# MK12_PIR.net
KiCad netlist of a schematic drawn in EAGLE
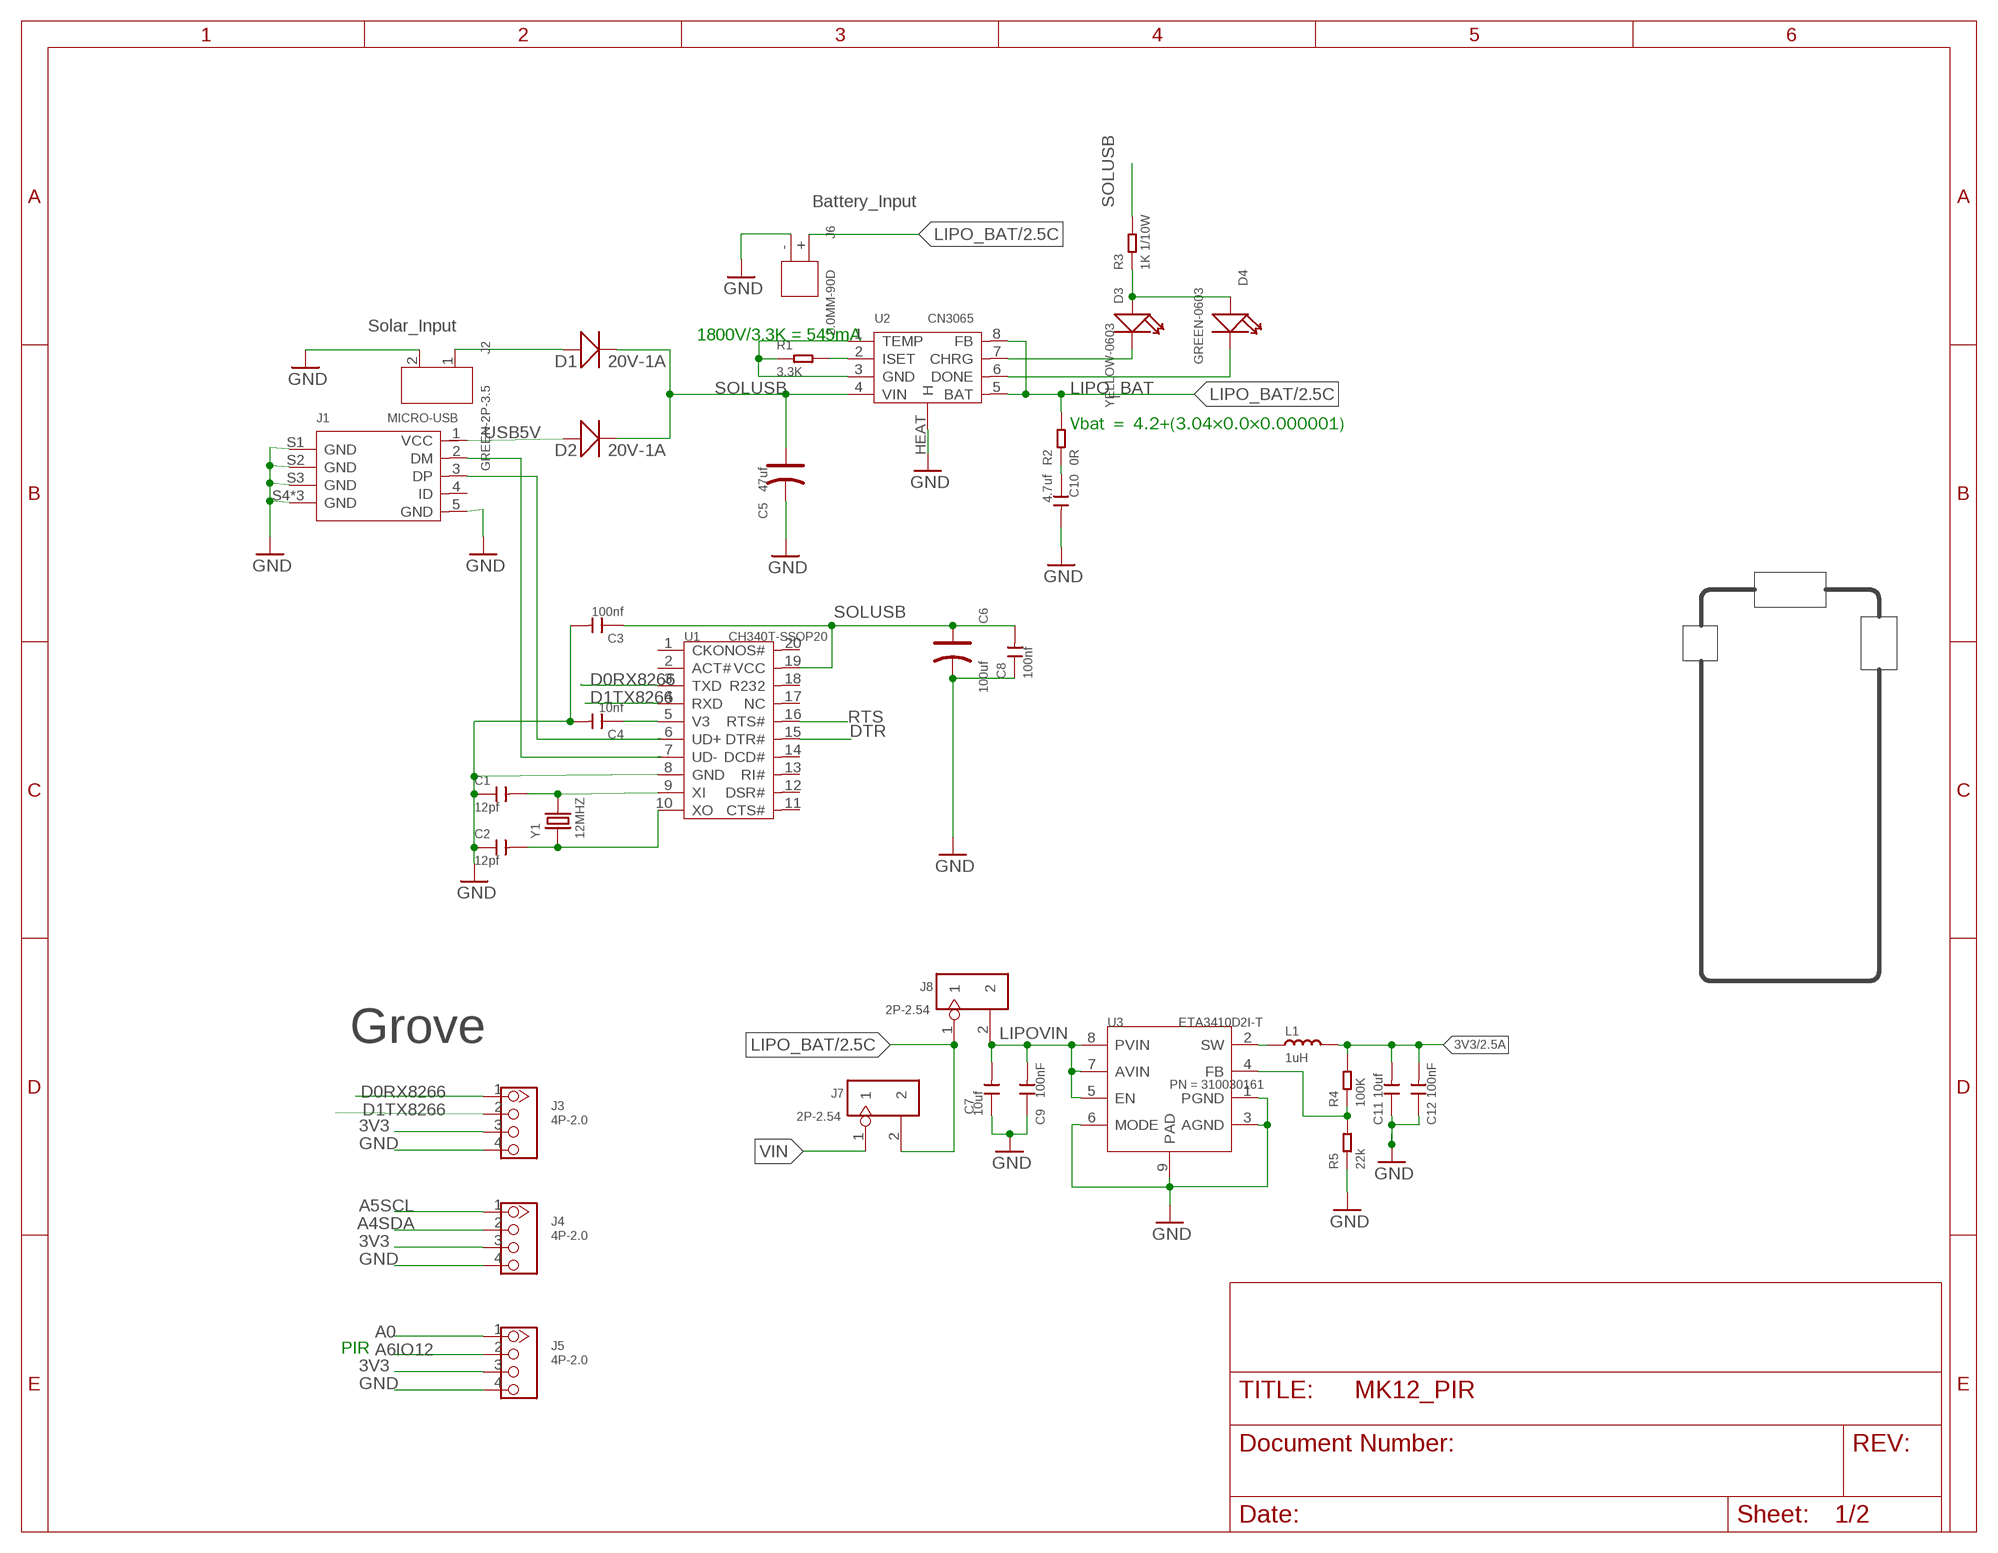
[diagram p0: schematic, sheet 1]
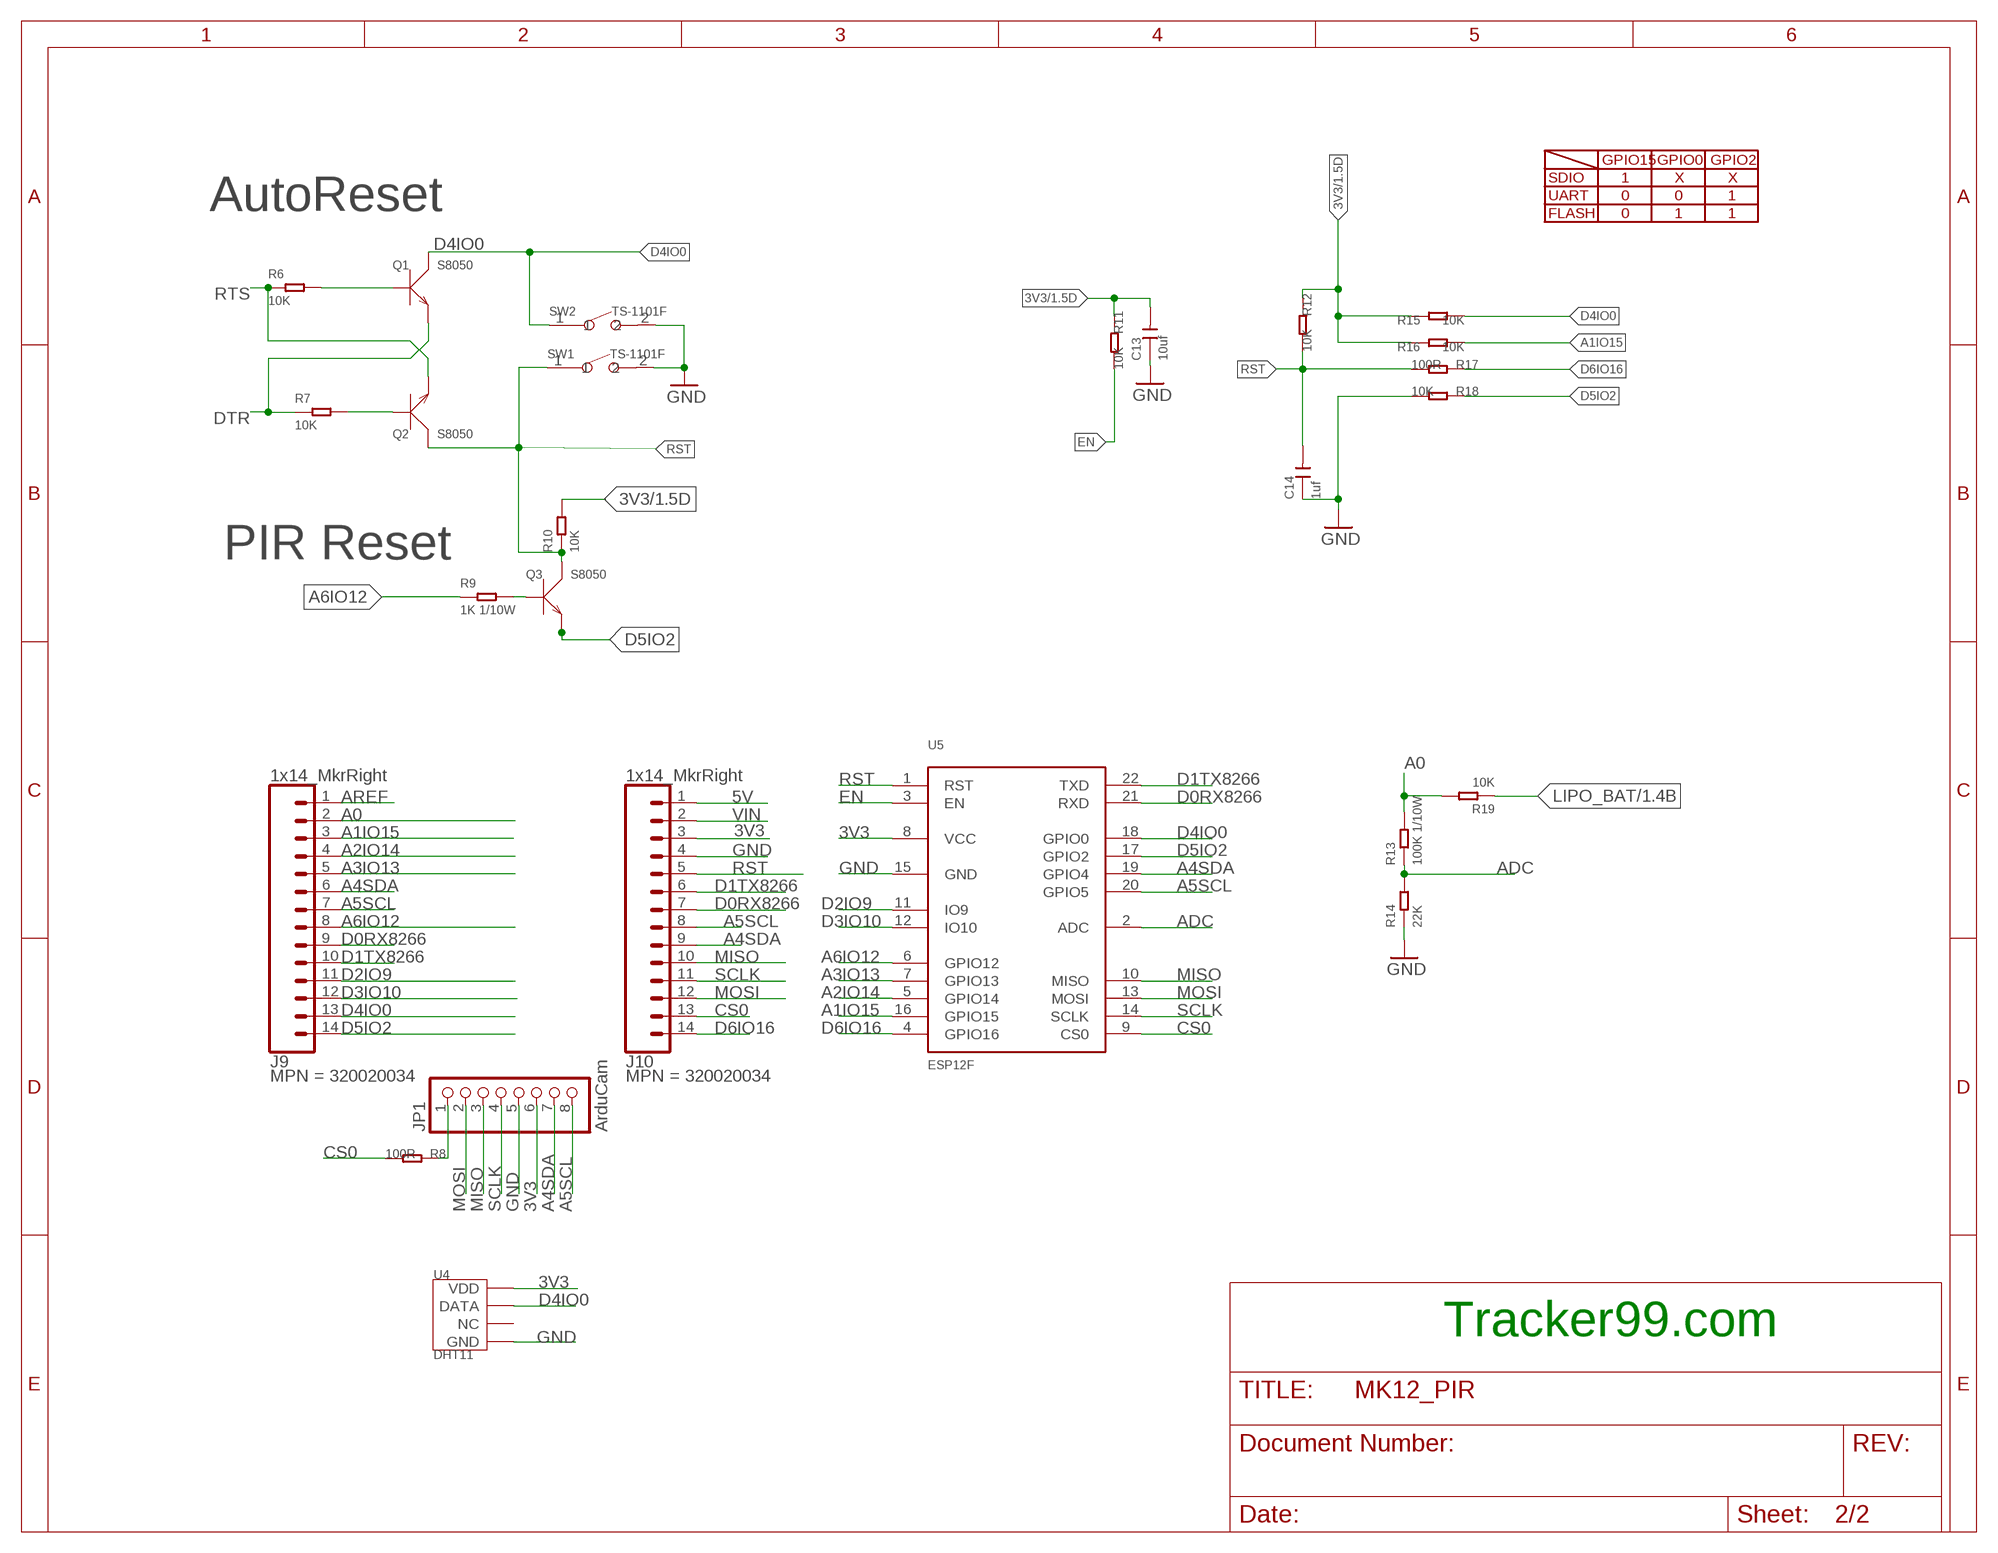
[diagram p1: schematic, sheet 2]

(export (version "E")
  (design (tool "Eeschema 10.0.6"))
  (components
    (comp (ref "C1")
      (value "12pf")
      (footprint "eagle-import:C0402")
      (fields (field (name "MPN") "CC0402JRNPO9BN120"))
      (libsource (lib "eagle-import") (part "CERAMIC-12PF-50V-5%-NPO(0402)"))
    )
    (comp (ref "C2")
      (value "12pf")
      (footprint "eagle-import:C0402")
      (fields (field (name "MPN") "CC0402JRNPO9BN120"))
      (libsource (lib "eagle-import") (part "CERAMIC-12PF-50V-5%-NPO(0402)"))
    )
    (comp (ref "C3")
      (value "100nf")
      (footprint "eagle-import:C0603")
      (fields (field (name "MPN") "CC0603KRX7R9BB104"))
      (libsource (lib "eagle-import") (part "CERAMIC-100NF-50V-10%-X7R(0603)"))
    )
    (comp (ref "C4")
      (value "10nf")
      (footprint "eagle-import:C0603")
      (fields (field (name "MPN") "CC0603KRX7R9BB103"))
      (libsource (lib "eagle-import") (part "CERAMIC-10NF-50V-10%-X7R(0603)"))
    )
    (comp (ref "C5")
      (value "47uf")
      (footprint "eagle-import:AVX-A")
      (fields (field (name "MPN") "TAJA476*006#NJ"))
      (libsource (lib "eagle-import") (part "TANTALUM-SMD-47UF-6.3V(AVX-A)"))
    )
    (comp (ref "C6")
      (value "100uf")
      (footprint "eagle-import:AVX-B")
      (fields (field (name "MPN") "TAJB107M010#NJ"))
      (libsource (lib "eagle-import") (part "TANTALUM-SMD-100UF-10V(AVX-B)"))
    )
    (comp (ref "C7")
      (value "10uf")
      (footprint "eagle-import:C0805")
      (fields (field (name "MPN") "CC0805KKX5R8BB106"))
      (libsource (lib "eagle-import") (part "CERAMIC-10UF-25V-10%-X5R(0805)"))
    )
    (comp (ref "C8")
      (value "100nf")
      (footprint "eagle-import:C0603")
      (fields (field (name "MPN") "CC0603KRX7R9BB104"))
      (libsource (lib "eagle-import") (part "CERAMIC-100NF-50V-10%-X7R(0603)"))
    )
    (comp (ref "C9")
      (value "100nF")
      (footprint "eagle-import:C0402")
      (libsource (lib "eagle-import") (part "CAP-0402"))
    )
    (comp (ref "C10")
      (value "4.7uf")
      (footprint "eagle-import:C0603")
      (fields (field (name "MPN") "CC0603KRX5R6BB475"))
      (libsource (lib "eagle-import") (part "CERAMIC-4.7UF-10V-10%-X5R(0603)"))
    )
    (comp (ref "C11")
      (value "10uf")
      (footprint "eagle-import:C0805")
      (fields (field (name "MPN") "CC0805KKX5R8BB106"))
      (libsource (lib "eagle-import") (part "CERAMIC-10UF-25V-10%-X5R(0805)"))
    )
    (comp (ref "C12")
      (value "100nF")
      (footprint "eagle-import:C0402")
      (libsource (lib "eagle-import") (part "CAP-0402"))
    )
    (comp (ref "D1")
      (value "20V-1A")
      (footprint "eagle-import:SOD-123")
      (fields (field (name "MPN") "B5819W"))
      (libsource (lib "eagle-import") (part "SMD-DIODE-SCHOTTKY-20V-1A(SOD-123)"))
    )
    (comp (ref "D2")
      (value "20V-1A")
      (footprint "eagle-import:SOD-123")
      (fields (field (name "MPN") "B5819W"))
      (libsource (lib "eagle-import") (part "SMD-DIODE-SCHOTTKY-20V-1A(SOD-123)"))
    )
    (comp (ref "D3")
      (value "YELLOW-0603")
      (footprint "eagle-import:LED-0603")
      (fields (field (name "MPN") "19-217-Y5C-AM1N1VY-3T"))
      (libsource (lib "eagle-import") (part "SMD-LED-CLEAR-YELLOW(0603)"))
    )
    (comp (ref "D4")
      (value "GREEN-0603")
      (footprint "eagle-import:LED-0603")
      (fields (field (name "MPN") "19-217-G7C-AN1P2-3T"))
      (libsource (lib "eagle-import") (part "SMD-LED-CLEAR-GREEN(0603)"))
    )
    (comp (ref "J1")
      (value "MICRO-USB")
      (footprint "eagle-import:MICRO-USB5+4P-SMD-0.65-B")
      (fields (field (name "EAGLEUP") "USB-MICROB;2.54mm"))
      (libsource (lib "eagle-import") (part "MICRO-USB5+4P'5+4P'"))
    )
    (comp (ref "J2")
      (value "GREEN-2P-3.5")
      (footprint "eagle-import:H2-3.5-7.0X7.0MM")
      (libsource (lib "eagle-import") (part "SCREW-TERMINAL-GREEN(2P-3.5)"))
    )
    (comp (ref "J3")
      (value "4P-2.0")
      (footprint "eagle-import:HW4-2.0")
      (libsource (lib "eagle-import") (part "GROVE-CONNECTOR-DIP(4P-2.0)"))
    )
    (comp (ref "J4")
      (value "4P-2.0")
      (footprint "eagle-import:HW4-2.0")
      (libsource (lib "eagle-import") (part "GROVE-CONNECTOR-DIP(4P-2.0)"))
    )
    (comp (ref "J5")
      (value "4P-2.0")
      (footprint "eagle-import:HW4-2.0")
      (libsource (lib "eagle-import") (part "GROVE-CONNECTOR-DIP(4P-2.0)"))
    )
    (comp (ref "J6")
      (value "2.0MM-90D")
      (footprint "eagle-import:H2-2.0-90D")
      (libsource (lib "eagle-import") (part "CONN-HEADER-PH-SIDE-(2P-2.0MM)'90D'"))
    )
    (comp (ref "J7")
      (value "2P-2.54")
      (footprint "eagle-import:H2-2.54")
      (fields (field (name "MPN") "P125-1102A0BS116A3"))
      (libsource (lib "eagle-import") (part "DIP-WHITE-MALE-HEADER-VERT(2P-2.54)"))
    )
    (comp (ref "J8")
      (value "2P-2.54")
      (footprint "eagle-import:H2-2.54")
      (fields (field (name "MPN") "P125-1102A0BS116A3"))
      (libsource (lib "eagle-import") (part "DIP-WHITE-MALE-HEADER-VERT(2P-2.54)"))
    )
    (comp (ref "L1")
      (value "1uH")
      (footprint "eagle-import:L0603")
      (libsource (lib "eagle-import") (part "INDUCTOR/FERRITE-BEAD'0603'"))
    )
    (comp (ref "R1")
      (value "3.3K")
      (footprint "eagle-import:R0603")
      (libsource (lib "eagle-import") (part "SMD-RES-3.3K-5%-1/10W(0603)"))
    )
    (comp (ref "R2")
      (value "0R")
      (footprint "eagle-import:R0603")
      (fields (field (name "MPN") "RC0603JR-070RL"))
      (libsource (lib "eagle-import") (part "SMD-RES-0R-5%-1/10W(0603)"))
    )
    (comp (ref "R3")
      (value "1K 1/10W")
      (footprint "eagle-import:R0603")
      (fields (field (name "MPN") "RC0603JR-071KL"))
      (libsource (lib "eagle-import") (part "SMD-RES-1K-5%-1/10W(0603)"))
    )
    (comp (ref "R4")
      (value "100K")
      (footprint "eagle-import:R0402")
      (fields (field (name "MPN") "RC0402FR-07100KL"))
      (libsource (lib "eagle-import") (part "SMD-RES-100K-1%-1/16W(0402)"))
    )
    (comp (ref "R5")
      (value "22k")
      (footprint "eagle-import:R0402")
      (fields (field (name "MPN") "RC0402FR-0722KL"))
      (libsource (lib "eagle-import") (part "SMD-RES-22K-1%-1/16W(0402)"))
    )
    (comp (ref "U1")
      (value "CH340T-SSOP20")
      (footprint "eagle-import:SSOP20-0.65-7.6X5.2MM")
      (fields (field (name "MPN") "CH340T"))
      (libsource (lib "eagle-import") (part "INTERFACE-CH340T(SSOP20)"))
    )
    (comp (ref "U2")
      (value "CN3065")
      (footprint "eagle-import:DFN-8")
      (libsource (lib "eagle-import") (part "PMIC-CN3065-DFN8"))
    )
    (comp (ref "U3")
      (value "ETA3410D2I-T")
      (footprint "eagle-import:DFN8G-0.5-2X2MM")
      (fields (field (name "PN") "310030161"))
      (libsource (lib "eagle-import") (part "CONVERTER-ETA3410"))
    )
    (comp (ref "Y1")
      (value "12MHZ")
      (footprint "eagle-import:X2-SMD-5.0X3.2X1.3MM")
      (fields (field (name "MPN") "5032/2P"))
      (libsource (lib "eagle-import") (part "SMD-CRYSTAL-12MHZ-20PF-20PPM-40R(2P-5.0X3.2MM)"))
    )
    (comp (ref "C13")
      (value "10uf")
      (footprint "eagle-import:C0603")
      (fields (field (name "MPN") "CC0603KRX5R6BB106"))
      (libsource (lib "eagle-import") (part "CERAMIC-10UF-10V-10%-X5R(0603)"))
    )
    (comp (ref "C14")
      (value "1uf")
      (footprint "eagle-import:C0603")
      (fields (field (name "MPN") "CC0603KRX7R8BB105"))
      (libsource (lib "eagle-import") (part "CERAMIC-1UF-25V-10%-X7R(0603)"))
    )
    (comp (ref "J9")
      (value "1x14_MkrRight")
      (footprint "eagle-import:1X14_LOCK")
      (fields (field (name "MPN") "320020034"))
      (libsource (lib "eagle-import") (part "CONN_14LOCK"))
    )
    (comp (ref "J10")
      (value "1x14_MkrRight")
      (footprint "eagle-import:1X14_LOCK")
      (fields (field (name "MPN") "320020034"))
      (libsource (lib "eagle-import") (part "CONN_14LOCK"))
    )
    (comp (ref "JP1")
      (value "ArduCam")
      (footprint "eagle-import:MILLER_1X08-LOCK")
      (libsource (lib "eagle-import") (part "MILLER_PINHD-1X8LOCK"))
    )
    (comp (ref "Q1")
      (value "S8050")
      (footprint "eagle-import:SOT-23")
      (libsource (lib "eagle-import") (part "SMD-TRANSISTORS-NPN-25V-500MW-S8050(SOT-23)"))
    )
    (comp (ref "Q2")
      (value "S8050")
      (footprint "eagle-import:SOT-23")
      (libsource (lib "eagle-import") (part "SMD-TRANSISTORS-NPN-25V-500MW-S8050(SOT-23)"))
    )
    (comp (ref "Q3")
      (value "S8050")
      (footprint "eagle-import:SOT-23")
      (libsource (lib "eagle-import") (part "SMD-TRANSISTORS-NPN-25V-500MW-S8050(SOT-23)"))
    )
    (comp (ref "R6")
      (value "10K")
      (footprint "eagle-import:R0402")
      (fields (field (name "MPN") "RC0402JR-0710KL"))
      (libsource (lib "eagle-import") (part "SMD-RES-10K-5%-1/(0402)"))
    )
    (comp (ref "R7")
      (value "10K")
      (footprint "eagle-import:R0402")
      (fields (field (name "MPN") "RC0402JR-0710KL"))
      (libsource (lib "eagle-import") (part "SMD-RES-10K-5%-1/(0402)"))
    )
    (comp (ref "R8")
      (value "100R")
      (footprint "eagle-import:R0603")
      (fields (field (name "MPN") "RC0603JR-07100RL"))
      (libsource (lib "eagle-import") (part "SMD-RES-100R-5%-1/10W(0603)"))
    )
    (comp (ref "R9")
      (value "1K 1/10W")
      (footprint "eagle-import:R0603")
      (fields (field (name "MPN") "RC0603JR-071KL"))
      (libsource (lib "eagle-import") (part "SMD-RES-1K-5%-1/10W(0603)"))
    )
    (comp (ref "R10")
      (value "10K")
      (footprint "eagle-import:R0402")
      (fields (field (name "MPN") "RC0402JR-0710KL"))
      (libsource (lib "eagle-import") (part "SMD-RES-10K-5%-1/(0402)"))
    )
    (comp (ref "R11")
      (value "10K")
      (footprint "eagle-import:SEEED-RESISTOR_R0402")
      (fields (field (name "MPN") "RC0402JR-0710KL"))
      (libsource (lib "eagle-import") (part "SEEED-RESISTOR_SMD-RES-10K-5%-1/(0402)"))
    )
    (comp (ref "R12")
      (value "10K")
      (footprint "eagle-import:SEEED-RESISTOR_R0402")
      (fields (field (name "MPN") "RC0402JR-0710KL"))
      (libsource (lib "eagle-import") (part "SEEED-RESISTOR_SMD-RES-10K-5%-1/(0402)"))
    )
    (comp (ref "R13")
      (value "100K 1/10W")
      (footprint "eagle-import:R0603")
      (fields (field (name "MPN") "RC0603JR-07100KL"))
      (libsource (lib "eagle-import") (part "SMD-RES-100K-5%-1/10W(0603)"))
    )
    (comp (ref "R14")
      (value "22K")
      (footprint "eagle-import:R0603")
      (fields (field (name "MPN") "RC0603JR-0722KL"))
      (libsource (lib "eagle-import") (part "SMD-RES-22K-5%-1/10W(0603)"))
    )
    (comp (ref "R15")
      (value "10K")
      (footprint "eagle-import:SEEED-RESISTOR_R0402")
      (fields (field (name "MPN") "RC0402JR-0710KL"))
      (libsource (lib "eagle-import") (part "SEEED-RESISTOR_SMD-RES-10K-5%-1/(0402)"))
    )
    (comp (ref "R16")
      (value "10K")
      (footprint "eagle-import:SEEED-RESISTOR_R0402")
      (fields (field (name "MPN") "RC0402JR-0710KL"))
      (libsource (lib "eagle-import") (part "SEEED-RESISTOR_SMD-RES-10K-5%-1/(0402)"))
    )
    (comp (ref "R17")
      (value "100R")
      (footprint "eagle-import:R0603")
      (fields (field (name "MPN") "RC0603JR-07100RL"))
      (libsource (lib "eagle-import") (part "SMD-RES-100R-5%-1/10W(0603)"))
    )
    (comp (ref "R18")
      (value "10K")
      (footprint "eagle-import:SEEED-RESISTOR_R0402")
      (fields (field (name "MPN") "RC0402JR-0710KL"))
      (libsource (lib "eagle-import") (part "SEEED-RESISTOR_SMD-RES-10K-5%-1/(0402)"))
    )
    (comp (ref "R19")
      (value "10K")
      (footprint "eagle-import:R0402")
      (fields (field (name "MPN") "RC0402JR-0710KL"))
      (libsource (lib "eagle-import") (part "SMD-RES-10K-5%-1/(0402)"))
    )
    (comp (ref "SW1")
      (value "TS-1101F")
      (footprint "eagle-import:SW2-5.0-6.0X3.0X4.3MM")
      (libsource (lib "eagle-import") (part "DIP-BUTTON(2P-6.0X3.0X4.3MM)-TS-1101F"))
    )
    (comp (ref "SW2")
      (value "TS-1101F")
      (footprint "eagle-import:SW2-5.0-6.0X3.0X4.3MM")
      (libsource (lib "eagle-import") (part "DIP-BUTTON(2P-6.0X3.0X4.3MM)-TS-1101F"))
    )
    (comp (ref "U4")
      (value "DHT11")
      (footprint "eagle-import:SNR4-2.54-15.5X12.0X5.5MM")
      (libsource (lib "eagle-import") (part "TEM-HUM-DHT11(4P-15.5X12.0MM)"))
    )
    (comp (ref "U5")
      (value "ESP12F")
      (footprint "eagle-import:ESP-12F")
      (libsource (lib "eagle-import") (part "ESP-12F"))
    )
  )
  (nets
    (net (code "1") (name "3V3") (class "Default")
      (node (ref "C11") (pin "2") (pinfunction "2_2") (pintype "passive"))
      (node (ref "C12") (pin "2") (pinfunction "2_2") (pintype "passive"))
      (node (ref "C13") (pin "2") (pinfunction "2_2") (pintype "passive"))
      (node (ref "J10") (pin "3") (pinfunction "3_3") (pintype "passive"))
      (node (ref "J3") (pin "3") (pinfunction "3_3") (pintype "bidirectional"))
      (node (ref "J4") (pin "3") (pinfunction "3_3") (pintype "bidirectional"))
      (node (ref "J5") (pin "3") (pinfunction "3_3") (pintype "bidirectional"))
      (node (ref "JP1") (pin "6") (pinfunction "6_6") (pintype "passive"))
      (node (ref "L1") (pin "2") (pinfunction "2_2") (pintype "passive"))
      (node (ref "R10") (pin "2") (pinfunction "2_2") (pintype "passive"))
      (node (ref "R11") (pin "1") (pinfunction "1_1") (pintype "passive"))
      (node (ref "R12") (pin "1") (pinfunction "1_1") (pintype "passive"))
      (node (ref "R15") (pin "1") (pinfunction "1_1") (pintype "passive"))
      (node (ref "R16") (pin "1") (pinfunction "1_1") (pintype "passive"))
      (node (ref "R4") (pin "2") (pinfunction "2_2") (pintype "passive"))
      (node (ref "U4") (pin "1") (pinfunction "VDD_1") (pintype "power_in"))
      (node (ref "U5") (pin "8") (pinfunction "VCC_8") (pintype "bidirectional"))
    )
    (net (code "2") (name "5V") (class "Default")
      (node (ref "J10") (pin "1") (pinfunction "1_1") (pintype "passive"))
    )
    (net (code "3") (name "A0") (class "Default")
      (node (ref "J5") (pin "1") (pinfunction "1_1") (pintype "bidirectional"))
      (node (ref "J9") (pin "2") (pinfunction "2_2") (pintype "passive"))
      (node (ref "R13") (pin "2") (pinfunction "2_2") (pintype "passive"))
      (node (ref "R19") (pin "2") (pinfunction "2_2") (pintype "passive"))
    )
    (net (code "4") (name "A1IO15") (class "Default")
      (node (ref "J9") (pin "3") (pinfunction "3_3") (pintype "passive"))
      (node (ref "R16") (pin "2") (pinfunction "2_2") (pintype "passive"))
      (node (ref "U5") (pin "16") (pinfunction "GPIO15_16") (pintype "bidirectional"))
    )
    (net (code "5") (name "A2IO14") (class "Default")
      (node (ref "J9") (pin "4") (pinfunction "4_4") (pintype "passive"))
      (node (ref "U5") (pin "5") (pinfunction "GPIO14_5") (pintype "bidirectional"))
    )
    (net (code "6") (name "A3IO13") (class "Default")
      (node (ref "J9") (pin "5") (pinfunction "5_5") (pintype "passive"))
      (node (ref "U5") (pin "7") (pinfunction "GPIO13_7") (pintype "bidirectional"))
    )
    (net (code "7") (name "A4SDA") (class "Default")
      (node (ref "J10") (pin "9") (pinfunction "9_9") (pintype "passive"))
      (node (ref "J4") (pin "2") (pinfunction "2_2") (pintype "bidirectional"))
      (node (ref "J9") (pin "6") (pinfunction "6_6") (pintype "passive"))
      (node (ref "JP1") (pin "7") (pinfunction "7_7") (pintype "passive"))
      (node (ref "U5") (pin "19") (pinfunction "GPIO4_19") (pintype "bidirectional"))
    )
    (net (code "8") (name "A5SCL") (class "Default")
      (node (ref "J10") (pin "8") (pinfunction "8_8") (pintype "passive"))
      (node (ref "J4") (pin "1") (pinfunction "1_1") (pintype "bidirectional"))
      (node (ref "J9") (pin "7") (pinfunction "7_7") (pintype "passive"))
      (node (ref "JP1") (pin "8") (pinfunction "8_8") (pintype "passive"))
      (node (ref "U5") (pin "20") (pinfunction "GPIO5_20") (pintype "bidirectional"))
    )
    (net (code "9") (name "A6IO12") (class "Default")
      (node (ref "J5") (pin "2") (pinfunction "2_2") (pintype "bidirectional"))
      (node (ref "J9") (pin "8") (pinfunction "8_8") (pintype "passive"))
      (node (ref "R9") (pin "1") (pinfunction "1_1") (pintype "passive"))
      (node (ref "U5") (pin "6") (pinfunction "GPIO12_6") (pintype "bidirectional"))
    )
    (net (code "10") (name "ADC") (class "Default")
      (node (ref "R13") (pin "1") (pinfunction "1_1") (pintype "passive"))
      (node (ref "R14") (pin "2") (pinfunction "2_2") (pintype "passive"))
      (node (ref "U5") (pin "2") (pinfunction "ADC_2") (pintype "bidirectional"))
    )
    (net (code "11") (name "AREF") (class "Default")
      (node (ref "J9") (pin "1") (pinfunction "1_1") (pintype "passive"))
    )
    (net (code "12") (name "CS0") (class "Default")
      (node (ref "J10") (pin "13") (pinfunction "13_13") (pintype "passive"))
      (node (ref "R8") (pin "2") (pinfunction "2_2") (pintype "passive"))
      (node (ref "U5") (pin "9") (pinfunction "CS0_9") (pintype "bidirectional"))
    )
    (net (code "13") (name "D0RX8266") (class "Default")
      (node (ref "J10") (pin "7") (pinfunction "7_7") (pintype "passive"))
      (node (ref "J3") (pin "1") (pinfunction "1_1") (pintype "bidirectional"))
      (node (ref "J9") (pin "9") (pinfunction "9_9") (pintype "passive"))
      (node (ref "U1") (pin "3") (pinfunction "TXD_3") (pintype "output"))
      (node (ref "U5") (pin "21") (pinfunction "RXD_21") (pintype "bidirectional"))
    )
    (net (code "14") (name "D1TX8266") (class "Default")
      (node (ref "J10") (pin "6") (pinfunction "6_6") (pintype "passive"))
      (node (ref "J3") (pin "2") (pinfunction "2_2") (pintype "bidirectional"))
      (node (ref "J9") (pin "10") (pinfunction "10_10") (pintype "passive"))
      (node (ref "U1") (pin "4") (pinfunction "RXD_4") (pintype "input"))
      (node (ref "U5") (pin "22") (pinfunction "TXD_22") (pintype "bidirectional"))
    )
    (net (code "15") (name "D2IO9") (class "Default")
      (node (ref "J9") (pin "11") (pinfunction "11_11") (pintype "passive"))
      (node (ref "U5") (pin "11") (pinfunction "IO9_11") (pintype "bidirectional"))
    )
    (net (code "16") (name "D3IO10") (class "Default")
      (node (ref "J9") (pin "12") (pinfunction "12_12") (pintype "passive"))
      (node (ref "U5") (pin "12") (pinfunction "IO10_12") (pintype "bidirectional"))
    )
    (net (code "17") (name "D4IO0") (class "Default")
      (node (ref "J9") (pin "13") (pinfunction "13_13") (pintype "passive"))
      (node (ref "Q1") (pin "3") (pinfunction "C_3") (pintype "passive"))
      (node (ref "R15") (pin "2") (pinfunction "2_2") (pintype "passive"))
      (node (ref "SW2") (pin "1") (pinfunction "1_1") (pintype "bidirectional"))
      (node (ref "U4") (pin "2") (pinfunction "DATA_2") (pintype "bidirectional"))
      (node (ref "U5") (pin "18") (pinfunction "GPIO0_18") (pintype "bidirectional"))
    )
    (net (code "18") (name "D5IO2") (class "Default")
      (node (ref "J9") (pin "14") (pinfunction "14_14") (pintype "passive"))
      (node (ref "Q3") (pin "2") (pinfunction "E_2") (pintype "passive"))
      (node (ref "R18") (pin "1") (pinfunction "1_1") (pintype "passive"))
      (node (ref "U5") (pin "17") (pinfunction "GPIO2_17") (pintype "bidirectional"))
    )
    (net (code "19") (name "D6IO16") (class "Default")
      (node (ref "J10") (pin "14") (pinfunction "14_14") (pintype "passive"))
      (node (ref "R17") (pin "1") (pinfunction "1_1") (pintype "passive"))
      (node (ref "U5") (pin "4") (pinfunction "GPIO16_4") (pintype "bidirectional"))
    )
    (net (code "20") (name "DTR") (class "Default")
      (node (ref "Q1") (pin "2") (pinfunction "E_2") (pintype "passive"))
      (node (ref "R7") (pin "1") (pinfunction "1_1") (pintype "passive"))
      (node (ref "U1") (pin "15") (pinfunction "DTR#_15") (pintype "output"))
    )
    (net (code "21") (name "EN") (class "Default")
      (node (ref "R11") (pin "2") (pinfunction "2_2") (pintype "passive"))
      (node (ref "U5") (pin "3") (pinfunction "EN_3") (pintype "bidirectional"))
    )
    (net (code "22") (name "GND") (class "Default")
      (node (ref "C1") (pin "1") (pinfunction "1_1") (pintype "passive"))
      (node (ref "C10") (pin "2") (pinfunction "2_2") (pintype "passive"))
      (node (ref "C11") (pin "1") (pinfunction "1_1") (pintype "passive"))
      (node (ref "C12") (pin "1") (pinfunction "1_1") (pintype "passive"))
      (node (ref "C13") (pin "1") (pinfunction "1_1") (pintype "passive"))
      (node (ref "C14") (pin "1") (pinfunction "1_1") (pintype "passive"))
      (node (ref "C2") (pin "1") (pinfunction "1_1") (pintype "passive"))
      (node (ref "C3") (pin "2") (pinfunction "2_2") (pintype "passive"))
      (node (ref "C4") (pin "2") (pinfunction "2_2") (pintype "passive"))
      (node (ref "C5") (pin "-") (pinfunction "-_-") (pintype "passive"))
      (node (ref "C6") (pin "-") (pinfunction "-_-") (pintype "passive"))
      (node (ref "C7") (pin "1") (pinfunction "1_1") (pintype "passive"))
      (node (ref "C8") (pin "1") (pinfunction "1_1") (pintype "passive"))
      (node (ref "C9") (pin "1") (pinfunction "1_1") (pintype "passive"))
      (node (ref "J1") (pin "5") (pinfunction "GND_5") (pintype "bidirectional"))
      (node (ref "J1") (pin "S1") (pinfunction "GND_S1") (pintype "bidirectional"))
      (node (ref "J1") (pin "S2") (pinfunction "GND_S2") (pintype "bidirectional"))
      (node (ref "J1") (pin "S3") (pinfunction "GND_S3") (pintype "bidirectional"))
      (node (ref "J1") (pin "S4") (pinfunction "GND_S4") (pintype "bidirectional"))
      (node (ref "J1") (pin "S5") (pinfunction "GND_S5") (pintype "bidirectional"))
      (node (ref "J1") (pin "S6") (pinfunction "GND_S6") (pintype "bidirectional"))
      (node (ref "J10") (pin "4") (pinfunction "4_4") (pintype "passive"))
      (node (ref "J2") (pin "2") (pinfunction "2_2") (pintype "bidirectional"))
      (node (ref "J3") (pin "4") (pinfunction "4_4") (pintype "bidirectional"))
      (node (ref "J4") (pin "4") (pinfunction "4_4") (pintype "bidirectional"))
      (node (ref "J5") (pin "4") (pinfunction "4_4") (pintype "bidirectional"))
      (node (ref "J6") (pin "-") (pinfunction "P$2_-") (pintype "bidirectional"))
      (node (ref "JP1") (pin "5") (pinfunction "5_5") (pintype "passive"))
      (node (ref "R1") (pin "1") (pinfunction "1_1") (pintype "passive"))
      (node (ref "R14") (pin "1") (pinfunction "1_1") (pintype "passive"))
      (node (ref "R18") (pin "2") (pinfunction "2_2") (pintype "passive"))
      (node (ref "R5") (pin "1") (pinfunction "1_1") (pintype "passive"))
      (node (ref "SW1") (pin "2") (pinfunction "2_2") (pintype "bidirectional"))
      (node (ref "SW2") (pin "2") (pinfunction "2_2") (pintype "bidirectional"))
      (node (ref "U1") (pin "8") (pinfunction "GND_8") (pintype "power_in"))
      (node (ref "U2") (pin "1") (pinfunction "TEMP_1") (pintype "input"))
      (node (ref "U2") (pin "3") (pinfunction "GND_3") (pintype "power_in"))
      (node (ref "U2") (pin "HEAT") (pinfunction "H_HEAT") (pintype "bidirectional"))
      (node (ref "U3") (pin "1") (pinfunction "PGND_1") (pintype "bidirectional"))
      (node (ref "U3") (pin "3") (pinfunction "AGND_3") (pintype "bidirectional"))
      (node (ref "U3") (pin "6") (pinfunction "MODE_6") (pintype "bidirectional"))
      (node (ref "U3") (pin "9") (pinfunction "PAD_9") (pintype "bidirectional"))
      (node (ref "U4") (pin "4") (pinfunction "GND_4") (pintype "power_in"))
      (node (ref "U5") (pin "15") (pinfunction "GND_15") (pintype "bidirectional"))
    )
    (net (code "23") (name "LIPOVIN") (class "Default")
      (node (ref "C7") (pin "2") (pinfunction "2_2") (pintype "passive"))
      (node (ref "C9") (pin "2") (pinfunction "2_2") (pintype "passive"))
      (node (ref "J8") (pin "2") (pinfunction "2_2") (pintype "bidirectional"))
      (node (ref "U3") (pin "5") (pinfunction "EN_5") (pintype "bidirectional"))
      (node (ref "U3") (pin "7") (pinfunction "AVIN_7") (pintype "bidirectional"))
      (node (ref "U3") (pin "8") (pinfunction "PVIN_8") (pintype "bidirectional"))
    )
    (net (code "24") (name "LIPO_BAT") (class "Default")
      (node (ref "J6") (pin "+") (pinfunction "P$1_+") (pintype "bidirectional"))
      (node (ref "J7") (pin "2") (pinfunction "2_2") (pintype "bidirectional"))
      (node (ref "J8") (pin "1") (pinfunction "1_1") (pintype "bidirectional"))
      (node (ref "R19") (pin "1") (pinfunction "1_1") (pintype "passive"))
      (node (ref "R2") (pin "2") (pinfunction "2_2") (pintype "passive"))
      (node (ref "U2") (pin "5") (pinfunction "BAT_5") (pintype "bidirectional"))
      (node (ref "U2") (pin "8") (pinfunction "FB_8") (pintype "input"))
    )
    (net (code "25") (name "MISO") (class "Default")
      (node (ref "J10") (pin "10") (pinfunction "10_10") (pintype "passive"))
      (node (ref "JP1") (pin "3") (pinfunction "3_3") (pintype "passive"))
      (node (ref "U5") (pin "10") (pinfunction "MISO_10") (pintype "bidirectional"))
    )
    (net (code "26") (name "MOSI") (class "Default")
      (node (ref "J10") (pin "12") (pinfunction "12_12") (pintype "passive"))
      (node (ref "JP1") (pin "2") (pinfunction "2_2") (pintype "passive"))
      (node (ref "U5") (pin "13") (pinfunction "MOSI_13") (pintype "bidirectional"))
    )
    (net (code "27") (name "NOS#") (class "Default")
      (node (ref "U1") (pin "20") (pinfunction "NOS#_20") (pintype "power_in"))
    )
    (net (code "28") (name "Net-(C10-Pad1)") (class "Default")
      (node (ref "C10") (pin "1") (pinfunction "1_1") (pintype "passive"))
      (node (ref "R2") (pin "1") (pinfunction "1_1") (pintype "passive"))
    )
    (net (code "29") (name "Net-(D1-Pad+)") (class "Default")
      (node (ref "D1") (pin "+") (pinfunction "+_+") (pintype "passive"))
      (node (ref "J2") (pin "1") (pinfunction "1_1") (pintype "bidirectional"))
    )
    (net (code "30") (name "Net-(D3-Pad+)") (class "Default")
      (node (ref "D3") (pin "+") (pinfunction "+_+") (pintype "passive"))
      (node (ref "D4") (pin "+") (pinfunction "+_+") (pintype "passive"))
      (node (ref "R3") (pin "1") (pinfunction "1_1") (pintype "passive"))
    )
    (net (code "31") (name "Net-(J1-DM)") (class "Default")
      (node (ref "J1") (pin "2") (pinfunction "DM_2") (pintype "bidirectional"))
      (node (ref "U1") (pin "7") (pinfunction "UD-_7") (pintype "bidirectional"))
    )
    (net (code "32") (name "Net-(J1-DP)") (class "Default")
      (node (ref "J1") (pin "3") (pinfunction "DP_3") (pintype "bidirectional"))
      (node (ref "U1") (pin "6") (pinfunction "UD+_6") (pintype "bidirectional"))
    )
    (net (code "33") (name "Net-(JP1-Pad1)") (class "Default")
      (node (ref "JP1") (pin "1") (pinfunction "1_1") (pintype "passive"))
      (node (ref "R8") (pin "1") (pinfunction "1_1") (pintype "passive"))
    )
    (net (code "34") (name "Net-(Q1-B)") (class "Default")
      (node (ref "Q1") (pin "1") (pinfunction "B_1") (pintype "passive"))
      (node (ref "R6") (pin "2") (pinfunction "2_2") (pintype "passive"))
    )
    (net (code "35") (name "Net-(Q2-B)") (class "Default")
      (node (ref "Q2") (pin "1") (pinfunction "B_1") (pintype "passive"))
      (node (ref "R7") (pin "2") (pinfunction "2_2") (pintype "passive"))
    )
    (net (code "36") (name "Net-(Q3-B)") (class "Default")
      (node (ref "Q3") (pin "1") (pinfunction "B_1") (pintype "passive"))
      (node (ref "R9") (pin "2") (pinfunction "2_2") (pintype "passive"))
    )
    (net (code "37") (name "Net-(Q3-C)") (class "Default")
      (node (ref "Q3") (pin "3") (pinfunction "C_3") (pintype "passive"))
      (node (ref "R10") (pin "1") (pinfunction "1_1") (pintype "passive"))
    )
    (net (code "38") (name "Net-(U1-V3)") (class "Default")
      (node (ref "C4") (pin "1") (pinfunction "1_1") (pintype "passive"))
      (node (ref "U1") (pin "5") (pinfunction "V3_5") (pintype "power_in"))
    )
    (net (code "39") (name "Net-(U1-XI)") (class "Default")
      (node (ref "C1") (pin "2") (pinfunction "2_2") (pintype "passive"))
      (node (ref "U1") (pin "9") (pinfunction "XI_9") (pintype "input"))
      (node (ref "Y1") (pin "2") (pinfunction "2_2") (pintype "passive"))
    )
    (net (code "40") (name "Net-(U1-XO)") (class "Default")
      (node (ref "C2") (pin "2") (pinfunction "2_2") (pintype "passive"))
      (node (ref "U1") (pin "10") (pinfunction "XO_10") (pintype "output"))
      (node (ref "Y1") (pin "1") (pinfunction "1_1") (pintype "passive"))
    )
    (net (code "41") (name "Net-(U2-CHRG)") (class "Default")
      (node (ref "D3") (pin "-") (pinfunction "-_-") (pintype "passive"))
      (node (ref "U2") (pin "7") (pinfunction "CHRG_7") (pintype "bidirectional"))
    )
    (net (code "42") (name "Net-(U2-DONE)") (class "Default")
      (node (ref "D4") (pin "-") (pinfunction "-_-") (pintype "passive"))
      (node (ref "U2") (pin "6") (pinfunction "DONE_6") (pintype "bidirectional"))
    )
    (net (code "43") (name "Net-(U2-ISET)") (class "Default")
      (node (ref "R1") (pin "2") (pinfunction "2_2") (pintype "passive"))
      (node (ref "U2") (pin "2") (pinfunction "ISET_2") (pintype "bidirectional"))
    )
    (net (code "44") (name "Net-(U3-FB)") (class "Default")
      (node (ref "R4") (pin "1") (pinfunction "1_1") (pintype "passive"))
      (node (ref "R5") (pin "2") (pinfunction "2_2") (pintype "passive"))
      (node (ref "U3") (pin "4") (pinfunction "FB_4") (pintype "bidirectional"))
    )
    (net (code "45") (name "Net-(U3-SW)") (class "Default")
      (node (ref "L1") (pin "1") (pinfunction "1_1") (pintype "passive"))
      (node (ref "U3") (pin "2") (pinfunction "SW_2") (pintype "bidirectional"))
    )
    (net (code "46") (name "RST") (class "Default")
      (node (ref "C14") (pin "2") (pinfunction "2_2") (pintype "passive"))
      (node (ref "J10") (pin "5") (pinfunction "5_5") (pintype "passive"))
      (node (ref "Q2") (pin "3") (pinfunction "C_3") (pintype "passive"))
      (node (ref "R12") (pin "2") (pinfunction "2_2") (pintype "passive"))
      (node (ref "R17") (pin "2") (pinfunction "2_2") (pintype "passive"))
      (node (ref "SW1") (pin "1") (pinfunction "1_1") (pintype "bidirectional"))
      (node (ref "U5") (pin "1") (pinfunction "RST_1") (pintype "bidirectional"))
    )
    (net (code "47") (name "RTS") (class "Default")
      (node (ref "Q2") (pin "2") (pinfunction "E_2") (pintype "passive"))
      (node (ref "R6") (pin "1") (pinfunction "1_1") (pintype "passive"))
      (node (ref "U1") (pin "16") (pinfunction "RTS#_16") (pintype "output"))
    )
    (net (code "48") (name "SCLK") (class "Default")
      (node (ref "J10") (pin "11") (pinfunction "11_11") (pintype "passive"))
      (node (ref "JP1") (pin "4") (pinfunction "4_4") (pintype "passive"))
      (node (ref "U5") (pin "14") (pinfunction "SCLK_14") (pintype "bidirectional"))
    )
    (net (code "49") (name "SOLUSB") (class "Default")
      (node (ref "C3") (pin "1") (pinfunction "1_1") (pintype "passive"))
      (node (ref "C5") (pin "+") (pinfunction "+_+") (pintype "passive"))
      (node (ref "C6") (pin "+") (pinfunction "+_+") (pintype "passive"))
      (node (ref "C8") (pin "2") (pinfunction "2_2") (pintype "passive"))
      (node (ref "D1") (pin "-") (pinfunction "-_-") (pintype "passive"))
      (node (ref "D2") (pin "-") (pinfunction "-_-") (pintype "passive"))
      (node (ref "R3") (pin "2") (pinfunction "2_2") (pintype "passive"))
      (node (ref "U1") (pin "19") (pinfunction "VCC_19") (pintype "power_in"))
      (node (ref "U2") (pin "4") (pinfunction "VIN_4") (pintype "input"))
    )
    (net (code "50") (name "USB5V") (class "Default")
      (node (ref "D2") (pin "+") (pinfunction "+_+") (pintype "passive"))
      (node (ref "J1") (pin "1") (pinfunction "VCC_1") (pintype "bidirectional"))
    )
    (net (code "51") (name "VIN") (class "Default")
      (node (ref "J10") (pin "2") (pinfunction "2_2") (pintype "passive"))
      (node (ref "J7") (pin "1") (pinfunction "1_1") (pintype "bidirectional"))
    )
    (net (code "52") (name "unconnected-(J1-ID-Pad4)") (class "Default")
      (node (ref "J1") (pin "4") (pinfunction "ID_4") (pintype "bidirectional"))
    )
    (net (code "53") (name "unconnected-(U1-ACT#-Pad2)") (class "Default")
      (node (ref "U1") (pin "2") (pinfunction "ACT#_2") (pintype "output"))
    )
    (net (code "54") (name "unconnected-(U1-CKO-Pad1)") (class "Default")
      (node (ref "U1") (pin "1") (pinfunction "CKO_1") (pintype "output"))
    )
    (net (code "55") (name "unconnected-(U1-CTS#-Pad11)") (class "Default")
      (node (ref "U1") (pin "11") (pinfunction "CTS#_11") (pintype "input"))
    )
    (net (code "56") (name "unconnected-(U1-DCD#-Pad14)") (class "Default")
      (node (ref "U1") (pin "14") (pinfunction "DCD#_14") (pintype "input"))
    )
    (net (code "57") (name "unconnected-(U1-DSR#-Pad12)") (class "Default")
      (node (ref "U1") (pin "12") (pinfunction "DSR#_12") (pintype "input"))
    )
    (net (code "58") (name "unconnected-(U1-NC-Pad17)") (class "Default")
      (node (ref "U1") (pin "17") (pinfunction "NC_17") (pintype "no_connect"))
    )
    (net (code "59") (name "unconnected-(U1-R232-Pad18)") (class "Default")
      (node (ref "U1") (pin "18") (pinfunction "R232_18") (pintype "input"))
    )
    (net (code "60") (name "unconnected-(U1-RI#-Pad13)") (class "Default")
      (node (ref "U1") (pin "13") (pinfunction "RI#_13") (pintype "input"))
    )
    (net (code "61") (name "unconnected-(U4-NC-Pad3)") (class "Default")
      (node (ref "U4") (pin "3") (pinfunction "NC_3") (pintype "no_connect"))
    )
  )
)
